# Schematic.net
KiCad netlist of a schematic drawn in EasyEDA
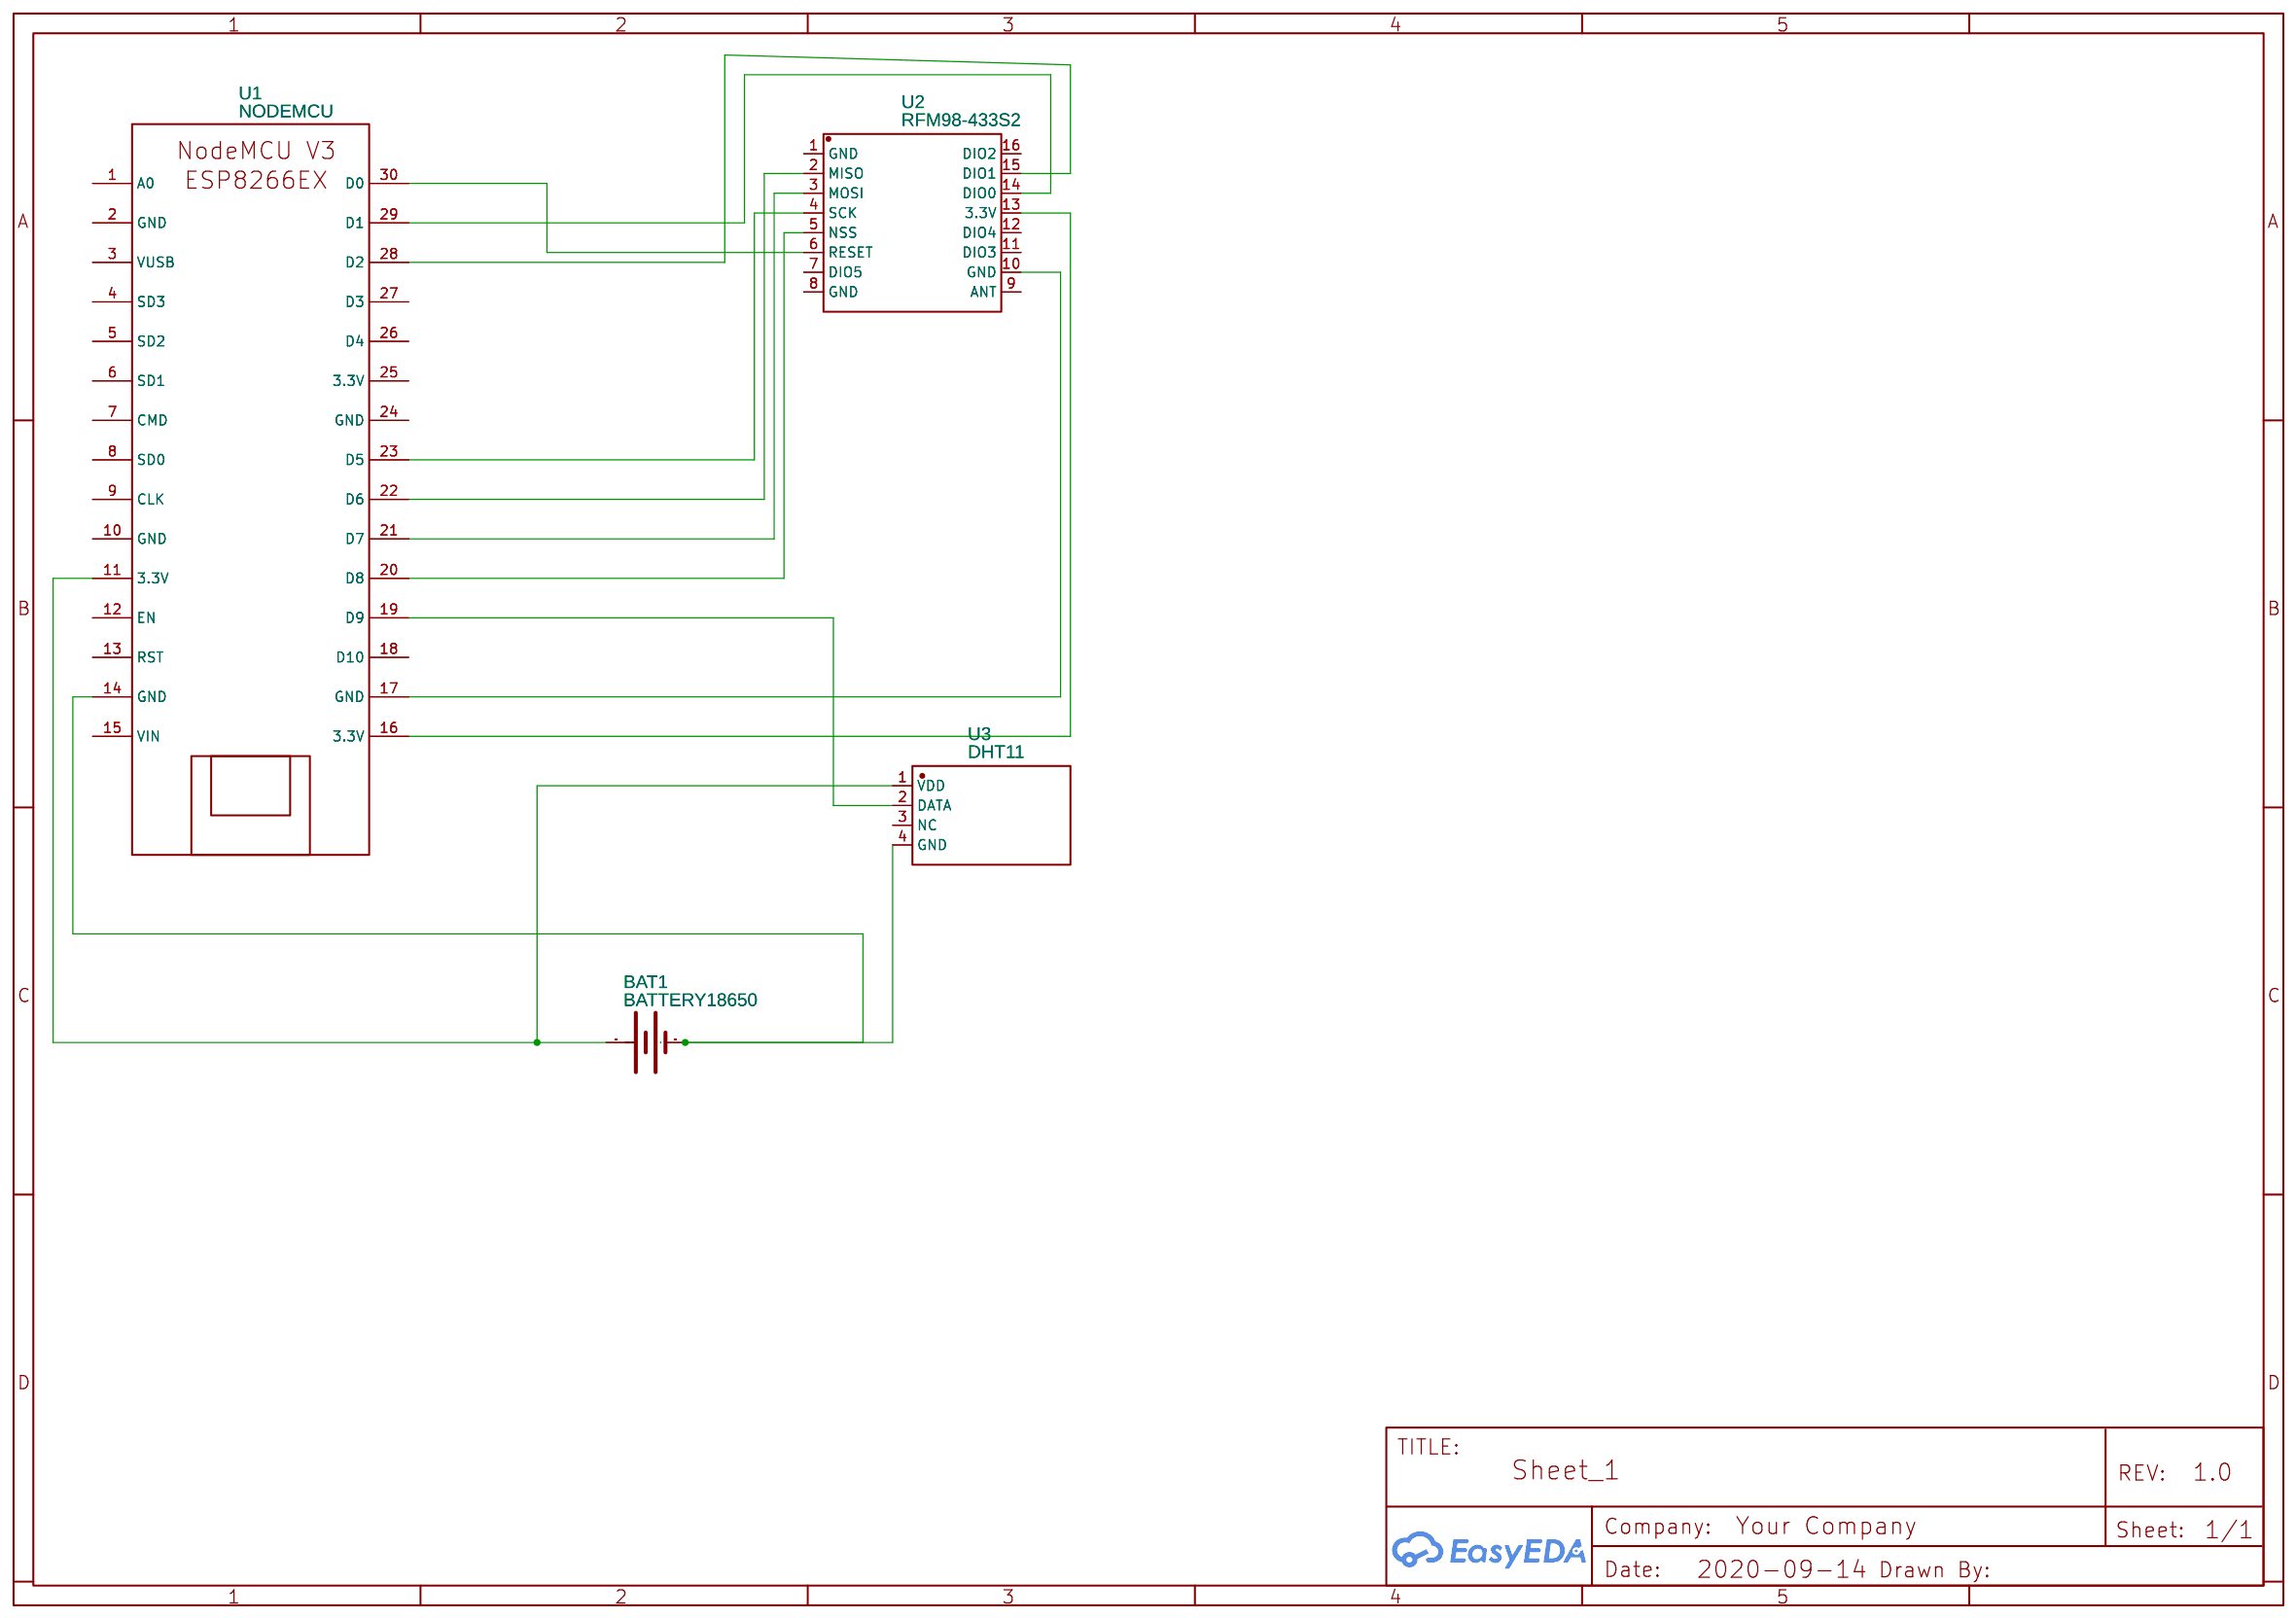
[diagram p0: schematic sheet]

(export (version "E")
  (design (tool "Eeschema 10.0.6"))
  (components
    (comp (ref "BAT1") (value "BATTERY18650") (libsource (lib "") (part "BATTERY18650")))
    (comp (ref "U1") (value "NODEMCU") (libsource (lib "") (part "NODEMCU")))
    (comp (ref "U2")
      (value "RFM98-433S2")
      (fields (field (name "BOM_Supplier Part") "C171661"))
      (libsource (lib "") (part "RFM98-433S2"))
    )
    (comp (ref "U3")
      (value "DHT11")
      (fields (field (name "BOM_Supplier Part") "C117051"))
      (libsource (lib "") (part "DHT11"))
    )
  )
  (nets
    (net (code "1") (name "Net-(BAT1-+)") (class "Default")
      (node (ref "BAT1") (pin "PWR@1") (pinfunction "+_PWR@1") (pintype "passive"))
      (node (ref "U1") (pin "11") (pinfunction "3.3V_11") (pintype "unspecified"))
      (node (ref "U3") (pin "1") (pinfunction "VDD_1") (pintype "unspecified"))
    )
    (net (code "2") (name "Net-(BAT1--)") (class "Default")
      (node (ref "BAT1") (pin "GND@1") (pinfunction "-_GND@1") (pintype "passive"))
      (node (ref "U1") (pin "14") (pinfunction "GND_14") (pintype "unspecified"))
      (node (ref "U3") (pin "4") (pinfunction "GND_4") (pintype "unspecified"))
    )
    (net (code "3") (name "Net-(U1-D0)") (class "Default")
      (node (ref "U1") (pin "30") (pinfunction "D0_30") (pintype "unspecified"))
      (node (ref "U2") (pin "6") (pinfunction "RESET_6") (pintype "unspecified"))
    )
    (net (code "4") (name "Net-(U1-D1)") (class "Default")
      (node (ref "U1") (pin "29") (pinfunction "D1_29") (pintype "unspecified"))
      (node (ref "U2") (pin "14") (pinfunction "DIO0_14") (pintype "unspecified"))
    )
    (net (code "5") (name "Net-(U1-D2)") (class "Default")
      (node (ref "U1") (pin "28") (pinfunction "D2_28") (pintype "unspecified"))
      (node (ref "U2") (pin "15") (pinfunction "DIO1_15") (pintype "unspecified"))
    )
    (net (code "6") (name "Net-(U1-D5)") (class "Default")
      (node (ref "U1") (pin "23") (pinfunction "D5_23") (pintype "unspecified"))
      (node (ref "U2") (pin "4") (pinfunction "SCK_4") (pintype "unspecified"))
    )
    (net (code "7") (name "Net-(U1-D6)") (class "Default")
      (node (ref "U1") (pin "22") (pinfunction "D6_22") (pintype "unspecified"))
      (node (ref "U2") (pin "2") (pinfunction "MISO_2") (pintype "unspecified"))
    )
    (net (code "8") (name "Net-(U1-D7)") (class "Default")
      (node (ref "U1") (pin "21") (pinfunction "D7_21") (pintype "unspecified"))
      (node (ref "U2") (pin "3") (pinfunction "MOSI_3") (pintype "unspecified"))
    )
    (net (code "9") (name "Net-(U1-D8)") (class "Default")
      (node (ref "U1") (pin "20") (pinfunction "D8_20") (pintype "unspecified"))
      (node (ref "U2") (pin "5") (pinfunction "NSS_5") (pintype "unspecified"))
    )
    (net (code "10") (name "Net-(U1-D9)") (class "Default")
      (node (ref "U1") (pin "19") (pinfunction "D9_19") (pintype "unspecified"))
      (node (ref "U3") (pin "2") (pinfunction "DATA_2") (pintype "unspecified"))
    )
    (net (code "11") (name "Net-(U1-GND-Pad17)") (class "Default")
      (node (ref "U1") (pin "17") (pinfunction "GND_17") (pintype "unspecified"))
      (node (ref "U2") (pin "10") (pinfunction "GND_10") (pintype "unspecified"))
    )
    (net (code "12") (name "Net-(U2-3.3V)") (class "Default")
      (node (ref "U1") (pin "16") (pinfunction "3.3V_16") (pintype "unspecified"))
      (node (ref "U2") (pin "13") (pinfunction "3.3V_13") (pintype "unspecified"))
    )
    (net (code "13") (name "unconnected-(U1-3.3V-Pad25)") (class "Default")
      (node (ref "U1") (pin "25") (pinfunction "3.3V_25") (pintype "unspecified"))
    )
    (net (code "14") (name "unconnected-(U1-A0-Pad1)") (class "Default")
      (node (ref "U1") (pin "1") (pinfunction "A0_1") (pintype "unspecified"))
    )
    (net (code "15") (name "unconnected-(U1-CLK-Pad9)") (class "Default")
      (node (ref "U1") (pin "9") (pinfunction "CLK_9") (pintype "unspecified"))
    )
    (net (code "16") (name "unconnected-(U1-CMD-Pad7)") (class "Default")
      (node (ref "U1") (pin "7") (pinfunction "CMD_7") (pintype "unspecified"))
    )
    (net (code "17") (name "unconnected-(U1-D3-Pad27)") (class "Default")
      (node (ref "U1") (pin "27") (pinfunction "D3_27") (pintype "unspecified"))
    )
    (net (code "18") (name "unconnected-(U1-D4-Pad26)") (class "Default")
      (node (ref "U1") (pin "26") (pinfunction "D4_26") (pintype "unspecified"))
    )
    (net (code "19") (name "unconnected-(U1-D10-Pad18)") (class "Default")
      (node (ref "U1") (pin "18") (pinfunction "D10_18") (pintype "unspecified"))
    )
    (net (code "20") (name "unconnected-(U1-EN-Pad12)") (class "Default")
      (node (ref "U1") (pin "12") (pinfunction "EN_12") (pintype "unspecified"))
    )
    (net (code "21") (name "unconnected-(U1-GND-Pad2)") (class "Default")
      (node (ref "U1") (pin "2") (pinfunction "GND_2") (pintype "unspecified"))
    )
    (net (code "22") (name "unconnected-(U1-GND-Pad10)") (class "Default")
      (node (ref "U1") (pin "10") (pinfunction "GND_10") (pintype "unspecified"))
    )
    (net (code "23") (name "unconnected-(U1-GND-Pad24)") (class "Default")
      (node (ref "U1") (pin "24") (pinfunction "GND_24") (pintype "unspecified"))
    )
    (net (code "24") (name "unconnected-(U1-RST-Pad13)") (class "Default")
      (node (ref "U1") (pin "13") (pinfunction "RST_13") (pintype "unspecified"))
    )
    (net (code "25") (name "unconnected-(U1-SD0-Pad8)") (class "Default")
      (node (ref "U1") (pin "8") (pinfunction "SD0_8") (pintype "unspecified"))
    )
    (net (code "26") (name "unconnected-(U1-SD1-Pad6)") (class "Default")
      (node (ref "U1") (pin "6") (pinfunction "SD1_6") (pintype "unspecified"))
    )
    (net (code "27") (name "unconnected-(U1-SD2-Pad5)") (class "Default")
      (node (ref "U1") (pin "5") (pinfunction "SD2_5") (pintype "unspecified"))
    )
    (net (code "28") (name "unconnected-(U1-SD3-Pad4)") (class "Default")
      (node (ref "U1") (pin "4") (pinfunction "SD3_4") (pintype "unspecified"))
    )
    (net (code "29") (name "unconnected-(U1-VIN-Pad15)") (class "Default")
      (node (ref "U1") (pin "15") (pinfunction "VIN_15") (pintype "unspecified"))
    )
    (net (code "30") (name "unconnected-(U1-VUSB-Pad3)") (class "Default")
      (node (ref "U1") (pin "3") (pinfunction "VUSB_3") (pintype "unspecified"))
    )
    (net (code "31") (name "unconnected-(U2-ANT-Pad9)") (class "Default")
      (node (ref "U2") (pin "9") (pinfunction "ANT_9") (pintype "unspecified"))
    )
    (net (code "32") (name "unconnected-(U2-DIO2-Pad16)") (class "Default")
      (node (ref "U2") (pin "16") (pinfunction "DIO2_16") (pintype "unspecified"))
    )
    (net (code "33") (name "unconnected-(U2-DIO3-Pad11)") (class "Default")
      (node (ref "U2") (pin "11") (pinfunction "DIO3_11") (pintype "unspecified"))
    )
    (net (code "34") (name "unconnected-(U2-DIO4-Pad12)") (class "Default")
      (node (ref "U2") (pin "12") (pinfunction "DIO4_12") (pintype "unspecified"))
    )
    (net (code "35") (name "unconnected-(U2-DIO5-Pad7)") (class "Default")
      (node (ref "U2") (pin "7") (pinfunction "DIO5_7") (pintype "unspecified"))
    )
    (net (code "36") (name "unconnected-(U2-GND-Pad1)") (class "Default")
      (node (ref "U2") (pin "1") (pinfunction "GND_1") (pintype "unspecified"))
    )
    (net (code "37") (name "unconnected-(U2-GND-Pad8)") (class "Default")
      (node (ref "U2") (pin "8") (pinfunction "GND_8") (pintype "unspecified"))
    )
    (net (code "38") (name "unconnected-(U3-NC-Pad3)") (class "Default")
      (node (ref "U3") (pin "3") (pinfunction "NC_3") (pintype "unspecified"))
    )
  )
)
